# MB_ZBT_memory.net
KiCad netlist of a schematic drawn in Altium Designer
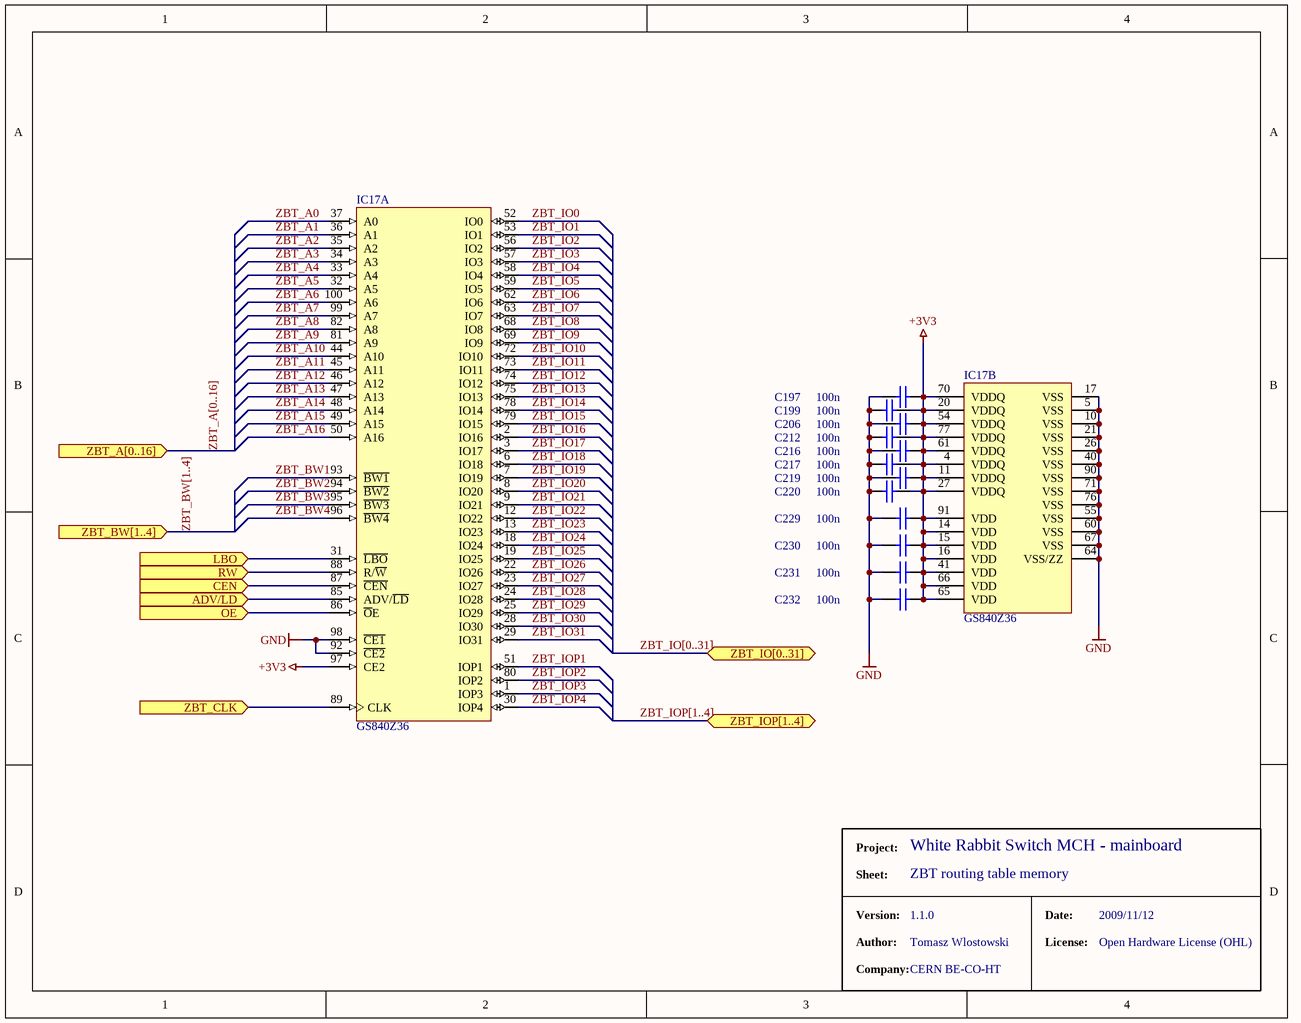
[diagram p0: MB_ZBT_memory.SchDoc]

(export (version "E")
  (design (tool "Eeschema 10.0.6"))
  (components
    (comp (ref "C197")
      (value "100n")
      (footprint "CAPC1005X55N")
      (description "Non-polarised capacitor")
      (fields
        (field (name "PART NUMBER") "CC0402_100NF_16V_10%_X7R")
        (field (name "VOLTAGE") "16V")
        (field (name "AUTHOR") "CERN DEM JLC")
      )
      (libsource (lib "Capacitors") (part "Capacitor - non polarized"))
    )
    (comp (ref "C199")
      (value "100n")
      (footprint "CAPC1005X55N")
      (description "Non-polarised capacitor")
      (fields
        (field (name "PART NUMBER") "CC0402_100NF_16V_10%_X7R")
        (field (name "VOLTAGE") "16V")
        (field (name "AUTHOR") "CERN DEM JLC")
      )
      (libsource (lib "Capacitors") (part "Capacitor - non polarized"))
    )
    (comp (ref "C206")
      (value "100n")
      (footprint "CAPC1005X55N")
      (description "Non-polarised capacitor")
      (fields
        (field (name "PART NUMBER") "CC0402_100NF_16V_10%_X7R")
        (field (name "VOLTAGE") "16V")
        (field (name "AUTHOR") "CERN DEM JLC")
      )
      (libsource (lib "Capacitors") (part "Capacitor - non polarized"))
    )
    (comp (ref "C212")
      (value "100n")
      (footprint "CAPC1005X55N")
      (description "Non-polarised capacitor")
      (fields
        (field (name "PART NUMBER") "CC0402_100NF_16V_10%_X7R")
        (field (name "VOLTAGE") "16V")
        (field (name "AUTHOR") "CERN DEM JLC")
      )
      (libsource (lib "Capacitors") (part "Capacitor - non polarized"))
    )
    (comp (ref "C216")
      (value "100n")
      (footprint "CAPC1005X55N")
      (description "Non-polarised capacitor")
      (fields
        (field (name "PART NUMBER") "CC0402_100NF_16V_10%_X7R")
        (field (name "VOLTAGE") "16V")
        (field (name "AUTHOR") "CERN DEM JLC")
      )
      (libsource (lib "Capacitors") (part "Capacitor - non polarized"))
    )
    (comp (ref "C217")
      (value "100n")
      (footprint "CAPC1005X55N")
      (description "Non-polarised capacitor")
      (fields
        (field (name "PART NUMBER") "CC0402_100NF_16V_10%_X7R")
        (field (name "VOLTAGE") "16V")
        (field (name "AUTHOR") "CERN DEM JLC")
      )
      (libsource (lib "Capacitors") (part "Capacitor - non polarized"))
    )
    (comp (ref "C219")
      (value "100n")
      (footprint "CAPC1005X55N")
      (description "Non-polarised capacitor")
      (fields
        (field (name "PART NUMBER") "CC0402_100NF_16V_10%_X7R")
        (field (name "VOLTAGE") "16V")
        (field (name "AUTHOR") "CERN DEM JLC")
      )
      (libsource (lib "Capacitors") (part "Capacitor - non polarized"))
    )
    (comp (ref "C220")
      (value "100n")
      (footprint "CAPC1005X55N")
      (description "Non-polarised capacitor")
      (fields
        (field (name "PART NUMBER") "CC0402_100NF_16V_10%_X7R")
        (field (name "VOLTAGE") "16V")
        (field (name "AUTHOR") "CERN DEM JLC")
      )
      (libsource (lib "Capacitors") (part "Capacitor - non polarized"))
    )
    (comp (ref "C229")
      (value "100n")
      (footprint "CAPC1005X55N")
      (description "Non-polarised capacitor")
      (fields
        (field (name "PART NUMBER") "CC0402_100NF_16V_10%_X7R")
        (field (name "VOLTAGE") "16V")
        (field (name "AUTHOR") "CERN DEM JLC")
      )
      (libsource (lib "Capacitors") (part "Capacitor - non polarized"))
    )
    (comp (ref "C230")
      (value "100n")
      (footprint "CAPC1005X55N")
      (description "Non-polarised capacitor")
      (fields
        (field (name "PART NUMBER") "CC0402_100NF_16V_10%_X7R")
        (field (name "VOLTAGE") "16V")
        (field (name "AUTHOR") "CERN DEM JLC")
      )
      (libsource (lib "Capacitors") (part "Capacitor - non polarized"))
    )
    (comp (ref "C231")
      (value "100n")
      (footprint "CAPC1005X55N")
      (description "Non-polarised capacitor")
      (fields
        (field (name "PART NUMBER") "CC0402_100NF_16V_10%_X7R")
        (field (name "VOLTAGE") "16V")
        (field (name "AUTHOR") "CERN DEM JLC")
      )
      (libsource (lib "Capacitors") (part "Capacitor - non polarized"))
    )
    (comp (ref "C232")
      (value "100n")
      (footprint "CAPC1005X55N")
      (description "Non-polarised capacitor")
      (fields
        (field (name "PART NUMBER") "CC0402_100NF_16V_10%_X7R")
        (field (name "VOLTAGE") "16V")
        (field (name "AUTHOR") "CERN DEM JLC")
      )
      (libsource (lib "Capacitors") (part "Capacitor - non polarized"))
    )
    (comp (ref "IC17")
      (value "GS840Z36")
      (footprint "TQFP100A101")
      (description "4.5 Mbit ZBT SRAM")
      (libsource (lib "wr_switch") (part "71V3556"))
    )
  )
  (nets
    (net (code "1") (name "+3V3") (class "Default")
      (node (ref "C197") (pin "2") (pinfunction "2_2") (pintype "passive"))
      (node (ref "C199") (pin "2") (pinfunction "2_2") (pintype "passive"))
      (node (ref "C206") (pin "2") (pinfunction "2_2") (pintype "passive"))
      (node (ref "C212") (pin "2") (pinfunction "2_2") (pintype "passive"))
      (node (ref "C216") (pin "2") (pinfunction "2_2") (pintype "passive"))
      (node (ref "C217") (pin "2") (pinfunction "2_2") (pintype "passive"))
      (node (ref "C219") (pin "2") (pinfunction "2_2") (pintype "passive"))
      (node (ref "C220") (pin "2") (pinfunction "2_2") (pintype "passive"))
      (node (ref "C229") (pin "2") (pinfunction "2_2") (pintype "passive"))
      (node (ref "C230") (pin "2") (pinfunction "2_2") (pintype "passive"))
      (node (ref "C231") (pin "2") (pinfunction "2_2") (pintype "passive"))
      (node (ref "C232") (pin "2") (pinfunction "2_2") (pintype "passive"))
      (node (ref "IC17") (pin "11") (pinfunction "VDDQ_11") (pintype "power_in"))
      (node (ref "IC17") (pin "14") (pinfunction "VDD_14") (pintype "power_in"))
      (node (ref "IC17") (pin "15") (pinfunction "VDD_15") (pintype "power_in"))
      (node (ref "IC17") (pin "16") (pinfunction "VDD_16") (pintype "power_in"))
      (node (ref "IC17") (pin "20") (pinfunction "VDDQ_20") (pintype "power_in"))
      (node (ref "IC17") (pin "27") (pinfunction "VDDQ_27") (pintype "power_in"))
      (node (ref "IC17") (pin "4") (pinfunction "VDDQ_4") (pintype "power_in"))
      (node (ref "IC17") (pin "41") (pinfunction "VDD_41") (pintype "power_in"))
      (node (ref "IC17") (pin "54") (pinfunction "VDDQ_54") (pintype "power_in"))
      (node (ref "IC17") (pin "61") (pinfunction "VDDQ_61") (pintype "power_in"))
      (node (ref "IC17") (pin "65") (pinfunction "VDD_65") (pintype "power_in"))
      (node (ref "IC17") (pin "66") (pinfunction "VDD_66") (pintype "power_in"))
      (node (ref "IC17") (pin "70") (pinfunction "VDDQ_70") (pintype "power_in"))
      (node (ref "IC17") (pin "77") (pinfunction "VDDQ_77") (pintype "power_in"))
      (node (ref "IC17") (pin "91") (pinfunction "VDD_91") (pintype "power_in"))
      (node (ref "IC17") (pin "97") (pinfunction "CE2_97") (pintype "input"))
    )
    (net (code "2") (name "/ADV{slash}LD") (class "Default")
      (node (ref "IC17") (pin "85") (pinfunction "ADV/~{LD}_85") (pintype "input"))
    )
    (net (code "3") (name "/CEN") (class "Default")
      (node (ref "IC17") (pin "87") (pinfunction "~{CEN}_87") (pintype "input"))
    )
    (net (code "4") (name "/LBO") (class "Default")
      (node (ref "IC17") (pin "31") (pinfunction "~{LBO}_31") (pintype "input"))
    )
    (net (code "5") (name "/OE") (class "Default")
      (node (ref "IC17") (pin "86") (pinfunction "~{O}E_86") (pintype "input"))
    )
    (net (code "6") (name "/RW") (class "Default")
      (node (ref "IC17") (pin "88") (pinfunction "R/~{W}_88") (pintype "input"))
    )
    (net (code "7") (name "/ZBT_A0") (class "Default")
      (node (ref "IC17") (pin "37") (pinfunction "A0_37") (pintype "input"))
    )
    (net (code "8") (name "/ZBT_A1") (class "Default")
      (node (ref "IC17") (pin "36") (pinfunction "A1_36") (pintype "input"))
    )
    (net (code "9") (name "/ZBT_A2") (class "Default")
      (node (ref "IC17") (pin "35") (pinfunction "A2_35") (pintype "input"))
    )
    (net (code "10") (name "/ZBT_A3") (class "Default")
      (node (ref "IC17") (pin "34") (pinfunction "A3_34") (pintype "input"))
    )
    (net (code "11") (name "/ZBT_A4") (class "Default")
      (node (ref "IC17") (pin "33") (pinfunction "A4_33") (pintype "input"))
    )
    (net (code "12") (name "/ZBT_A5") (class "Default")
      (node (ref "IC17") (pin "32") (pinfunction "A5_32") (pintype "input"))
    )
    (net (code "13") (name "/ZBT_A6") (class "Default")
      (node (ref "IC17") (pin "100") (pinfunction "A6_100") (pintype "input"))
    )
    (net (code "14") (name "/ZBT_A7") (class "Default")
      (node (ref "IC17") (pin "99") (pinfunction "A7_99") (pintype "input"))
    )
    (net (code "15") (name "/ZBT_A8") (class "Default")
      (node (ref "IC17") (pin "82") (pinfunction "A8_82") (pintype "input"))
    )
    (net (code "16") (name "/ZBT_A9") (class "Default")
      (node (ref "IC17") (pin "81") (pinfunction "A9_81") (pintype "input"))
    )
    (net (code "17") (name "/ZBT_A10") (class "Default")
      (node (ref "IC17") (pin "44") (pinfunction "A10_44") (pintype "input"))
    )
    (net (code "18") (name "/ZBT_A11") (class "Default")
      (node (ref "IC17") (pin "45") (pinfunction "A11_45") (pintype "input"))
    )
    (net (code "19") (name "/ZBT_A12") (class "Default")
      (node (ref "IC17") (pin "46") (pinfunction "A12_46") (pintype "input"))
    )
    (net (code "20") (name "/ZBT_A13") (class "Default")
      (node (ref "IC17") (pin "47") (pinfunction "A13_47") (pintype "input"))
    )
    (net (code "21") (name "/ZBT_A14") (class "Default")
      (node (ref "IC17") (pin "48") (pinfunction "A14_48") (pintype "input"))
    )
    (net (code "22") (name "/ZBT_A15") (class "Default")
      (node (ref "IC17") (pin "49") (pinfunction "A15_49") (pintype "input"))
    )
    (net (code "23") (name "/ZBT_A16") (class "Default")
      (node (ref "IC17") (pin "50") (pinfunction "A16_50") (pintype "input"))
    )
    (net (code "25") (name "/ZBT_BW1") (class "Default")
      (node (ref "IC17") (pin "93") (pinfunction "~{BW1}_93") (pintype "input"))
    )
    (net (code "26") (name "/ZBT_BW2") (class "Default")
      (node (ref "IC17") (pin "94") (pinfunction "~{BW2}_94") (pintype "input"))
    )
    (net (code "27") (name "/ZBT_BW3") (class "Default")
      (node (ref "IC17") (pin "95") (pinfunction "~{BW3}_95") (pintype "input"))
    )
    (net (code "28") (name "/ZBT_BW4") (class "Default")
      (node (ref "IC17") (pin "96") (pinfunction "~{BW4}_96") (pintype "input"))
    )
    (net (code "30") (name "/ZBT_CLK") (class "Default")
      (node (ref "IC17") (pin "89") (pinfunction "CLK_89") (pintype "input"))
    )
    (net (code "31") (name "/ZBT_IO0") (class "Default")
      (node (ref "IC17") (pin "52") (pinfunction "IO0_52") (pintype "bidirectional"))
    )
    (net (code "32") (name "/ZBT_IO1") (class "Default")
      (node (ref "IC17") (pin "53") (pinfunction "IO1_53") (pintype "bidirectional"))
    )
    (net (code "33") (name "/ZBT_IO2") (class "Default")
      (node (ref "IC17") (pin "56") (pinfunction "IO2_56") (pintype "bidirectional"))
    )
    (net (code "34") (name "/ZBT_IO3") (class "Default")
      (node (ref "IC17") (pin "57") (pinfunction "IO3_57") (pintype "bidirectional"))
    )
    (net (code "35") (name "/ZBT_IO4") (class "Default")
      (node (ref "IC17") (pin "58") (pinfunction "IO4_58") (pintype "bidirectional"))
    )
    (net (code "36") (name "/ZBT_IO5") (class "Default")
      (node (ref "IC17") (pin "59") (pinfunction "IO5_59") (pintype "bidirectional"))
    )
    (net (code "37") (name "/ZBT_IO6") (class "Default")
      (node (ref "IC17") (pin "62") (pinfunction "IO6_62") (pintype "bidirectional"))
    )
    (net (code "38") (name "/ZBT_IO7") (class "Default")
      (node (ref "IC17") (pin "63") (pinfunction "IO7_63") (pintype "bidirectional"))
    )
    (net (code "39") (name "/ZBT_IO8") (class "Default")
      (node (ref "IC17") (pin "68") (pinfunction "IO8_68") (pintype "bidirectional"))
    )
    (net (code "40") (name "/ZBT_IO9") (class "Default")
      (node (ref "IC17") (pin "69") (pinfunction "IO9_69") (pintype "bidirectional"))
    )
    (net (code "41") (name "/ZBT_IO10") (class "Default")
      (node (ref "IC17") (pin "72") (pinfunction "IO10_72") (pintype "bidirectional"))
    )
    (net (code "42") (name "/ZBT_IO11") (class "Default")
      (node (ref "IC17") (pin "73") (pinfunction "IO11_73") (pintype "bidirectional"))
    )
    (net (code "43") (name "/ZBT_IO12") (class "Default")
      (node (ref "IC17") (pin "74") (pinfunction "IO12_74") (pintype "bidirectional"))
    )
    (net (code "44") (name "/ZBT_IO13") (class "Default")
      (node (ref "IC17") (pin "75") (pinfunction "IO13_75") (pintype "bidirectional"))
    )
    (net (code "45") (name "/ZBT_IO14") (class "Default")
      (node (ref "IC17") (pin "78") (pinfunction "IO14_78") (pintype "bidirectional"))
    )
    (net (code "46") (name "/ZBT_IO15") (class "Default")
      (node (ref "IC17") (pin "79") (pinfunction "IO15_79") (pintype "bidirectional"))
    )
    (net (code "47") (name "/ZBT_IO16") (class "Default")
      (node (ref "IC17") (pin "2") (pinfunction "IO16_2") (pintype "bidirectional"))
    )
    (net (code "48") (name "/ZBT_IO17") (class "Default")
      (node (ref "IC17") (pin "3") (pinfunction "IO17_3") (pintype "bidirectional"))
    )
    (net (code "49") (name "/ZBT_IO18") (class "Default")
      (node (ref "IC17") (pin "6") (pinfunction "IO18_6") (pintype "bidirectional"))
    )
    (net (code "50") (name "/ZBT_IO19") (class "Default")
      (node (ref "IC17") (pin "7") (pinfunction "IO19_7") (pintype "bidirectional"))
    )
    (net (code "51") (name "/ZBT_IO20") (class "Default")
      (node (ref "IC17") (pin "8") (pinfunction "IO20_8") (pintype "bidirectional"))
    )
    (net (code "52") (name "/ZBT_IO21") (class "Default")
      (node (ref "IC17") (pin "9") (pinfunction "IO21_9") (pintype "bidirectional"))
    )
    (net (code "53") (name "/ZBT_IO22") (class "Default")
      (node (ref "IC17") (pin "12") (pinfunction "IO22_12") (pintype "bidirectional"))
    )
    (net (code "54") (name "/ZBT_IO23") (class "Default")
      (node (ref "IC17") (pin "13") (pinfunction "IO23_13") (pintype "bidirectional"))
    )
    (net (code "55") (name "/ZBT_IO24") (class "Default")
      (node (ref "IC17") (pin "18") (pinfunction "IO24_18") (pintype "bidirectional"))
    )
    (net (code "56") (name "/ZBT_IO25") (class "Default")
      (node (ref "IC17") (pin "19") (pinfunction "IO25_19") (pintype "bidirectional"))
    )
    (net (code "57") (name "/ZBT_IO26") (class "Default")
      (node (ref "IC17") (pin "22") (pinfunction "IO26_22") (pintype "bidirectional"))
    )
    (net (code "58") (name "/ZBT_IO27") (class "Default")
      (node (ref "IC17") (pin "23") (pinfunction "IO27_23") (pintype "bidirectional"))
    )
    (net (code "59") (name "/ZBT_IO28") (class "Default")
      (node (ref "IC17") (pin "24") (pinfunction "IO28_24") (pintype "bidirectional"))
    )
    (net (code "60") (name "/ZBT_IO29") (class "Default")
      (node (ref "IC17") (pin "25") (pinfunction "IO29_25") (pintype "bidirectional"))
    )
    (net (code "61") (name "/ZBT_IO30") (class "Default")
      (node (ref "IC17") (pin "28") (pinfunction "IO30_28") (pintype "bidirectional"))
    )
    (net (code "62") (name "/ZBT_IO31") (class "Default")
      (node (ref "IC17") (pin "29") (pinfunction "IO31_29") (pintype "bidirectional"))
    )
    (net (code "63") (name "/ZBT_IOP1") (class "Default")
      (node (ref "IC17") (pin "51") (pinfunction "IOP1_51") (pintype "bidirectional"))
    )
    (net (code "64") (name "/ZBT_IOP2") (class "Default")
      (node (ref "IC17") (pin "80") (pinfunction "IOP2_80") (pintype "bidirectional"))
    )
    (net (code "65") (name "/ZBT_IOP3") (class "Default")
      (node (ref "IC17") (pin "1") (pinfunction "IOP3_1") (pintype "bidirectional"))
    )
    (net (code "66") (name "/ZBT_IOP4") (class "Default")
      (node (ref "IC17") (pin "30") (pinfunction "IOP4_30") (pintype "bidirectional"))
    )
    (net (code "69") (name "GND") (class "Default")
      (node (ref "C197") (pin "1") (pinfunction "1_1") (pintype "passive"))
      (node (ref "C199") (pin "1") (pinfunction "1_1") (pintype "passive"))
      (node (ref "C206") (pin "1") (pinfunction "1_1") (pintype "passive"))
      (node (ref "C212") (pin "1") (pinfunction "1_1") (pintype "passive"))
      (node (ref "C216") (pin "1") (pinfunction "1_1") (pintype "passive"))
      (node (ref "C217") (pin "1") (pinfunction "1_1") (pintype "passive"))
      (node (ref "C219") (pin "1") (pinfunction "1_1") (pintype "passive"))
      (node (ref "C220") (pin "1") (pinfunction "1_1") (pintype "passive"))
      (node (ref "C229") (pin "1") (pinfunction "1_1") (pintype "passive"))
      (node (ref "C230") (pin "1") (pinfunction "1_1") (pintype "passive"))
      (node (ref "C231") (pin "1") (pinfunction "1_1") (pintype "passive"))
      (node (ref "C232") (pin "1") (pinfunction "1_1") (pintype "passive"))
      (node (ref "IC17") (pin "10") (pinfunction "VSS_10") (pintype "power_in"))
      (node (ref "IC17") (pin "17") (pinfunction "VSS_17") (pintype "power_in"))
      (node (ref "IC17") (pin "21") (pinfunction "VSS_21") (pintype "power_in"))
      (node (ref "IC17") (pin "26") (pinfunction "VSS_26") (pintype "power_in"))
      (node (ref "IC17") (pin "40") (pinfunction "VSS_40") (pintype "power_in"))
      (node (ref "IC17") (pin "5") (pinfunction "VSS_5") (pintype "power_in"))
      (node (ref "IC17") (pin "55") (pinfunction "VSS_55") (pintype "power_in"))
      (node (ref "IC17") (pin "60") (pinfunction "VSS_60") (pintype "power_in"))
      (node (ref "IC17") (pin "64") (pinfunction "VSS/ZZ_64") (pintype "power_in"))
      (node (ref "IC17") (pin "67") (pinfunction "VSS_67") (pintype "power_in"))
      (node (ref "IC17") (pin "71") (pinfunction "VSS_71") (pintype "power_in"))
      (node (ref "IC17") (pin "76") (pinfunction "VSS_76") (pintype "power_in"))
      (node (ref "IC17") (pin "90") (pinfunction "VSS_90") (pintype "power_in"))
      (node (ref "IC17") (pin "92") (pinfunction "~{CE2}_92") (pintype "input"))
      (node (ref "IC17") (pin "98") (pinfunction "~{CE1}_98") (pintype "input"))
    )
  )
)
